# HMS_Olfactometer_v2_3.net
KiCad netlist of a schematic drawn in EAGLE
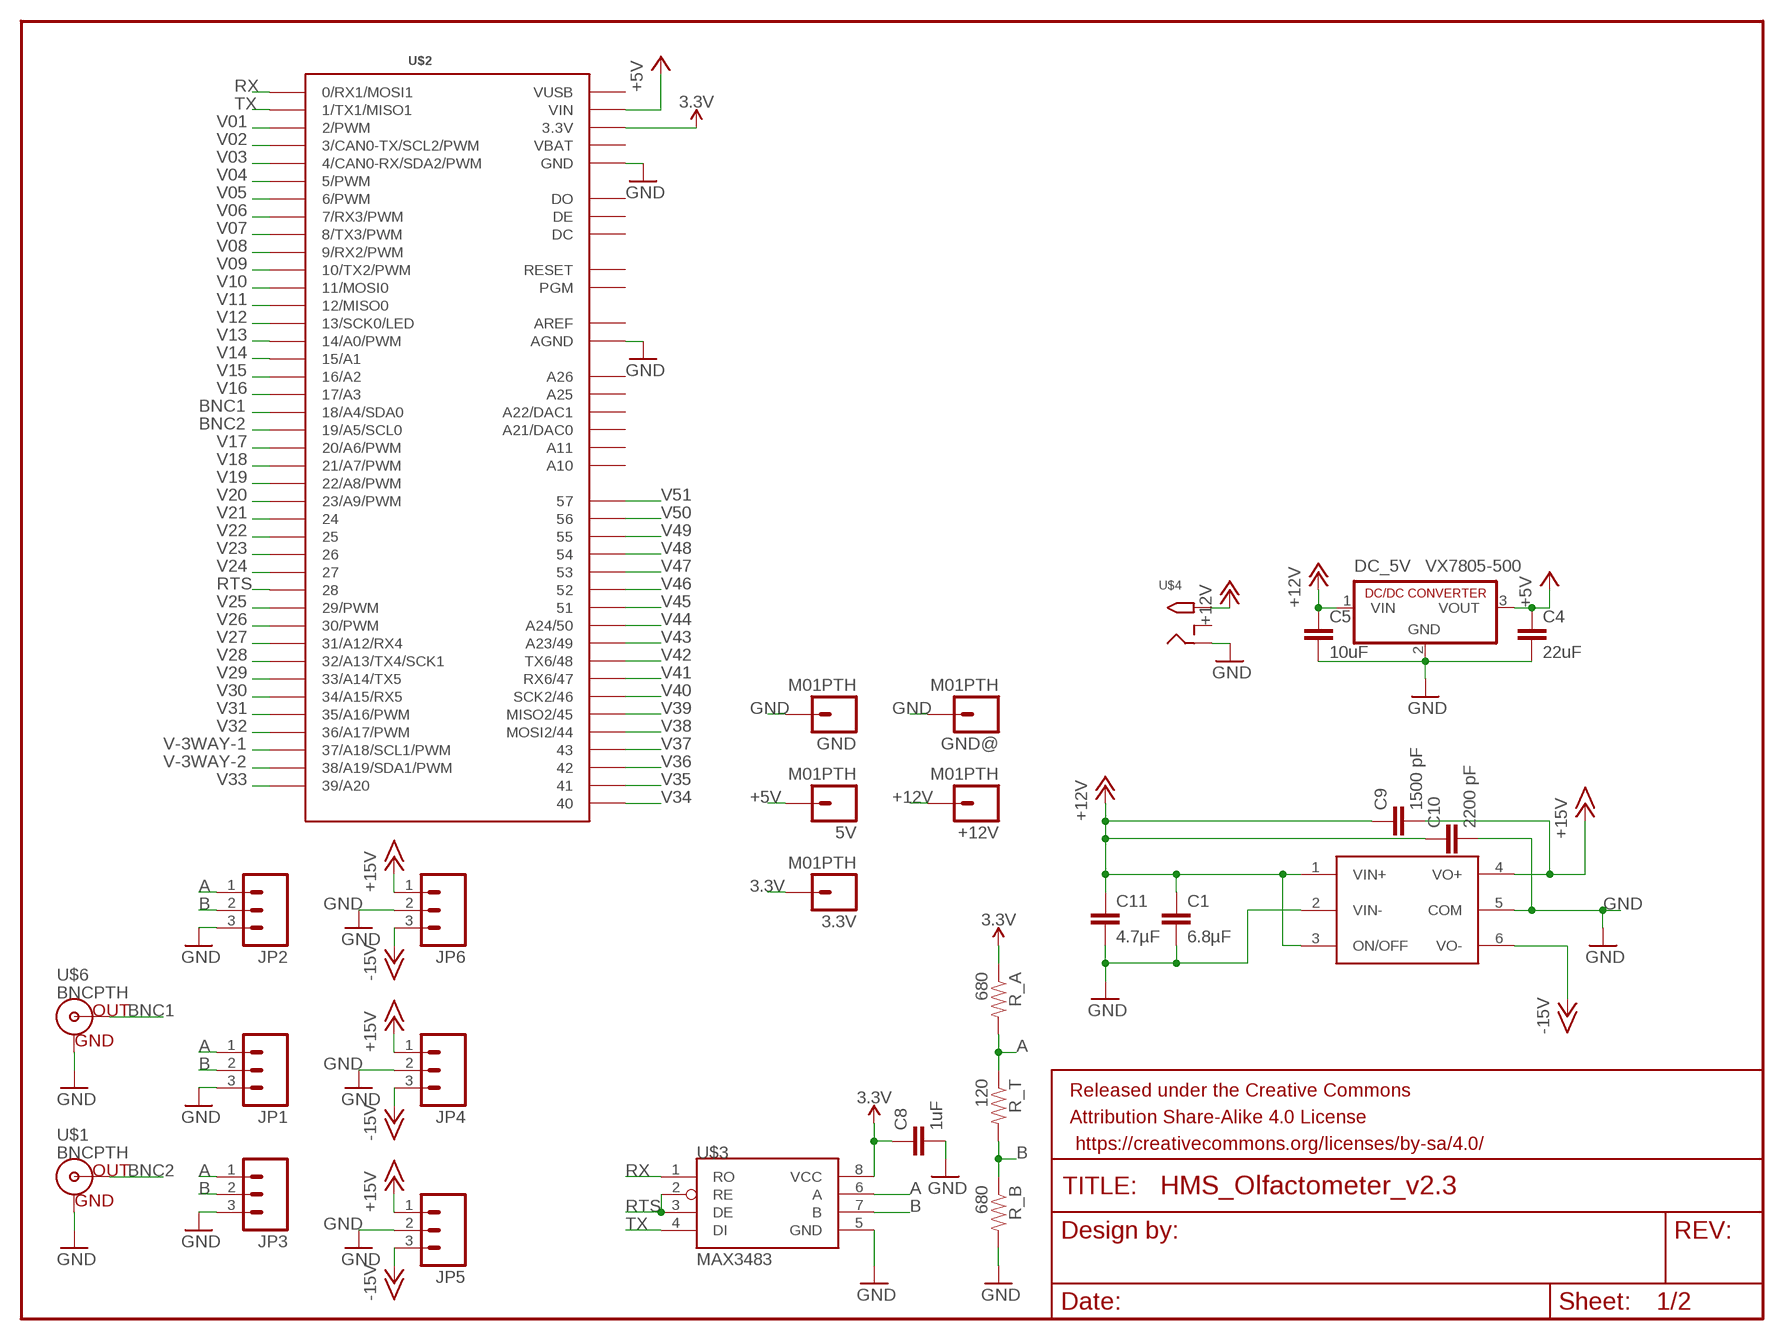
[diagram p0: schematic, sheet 1]
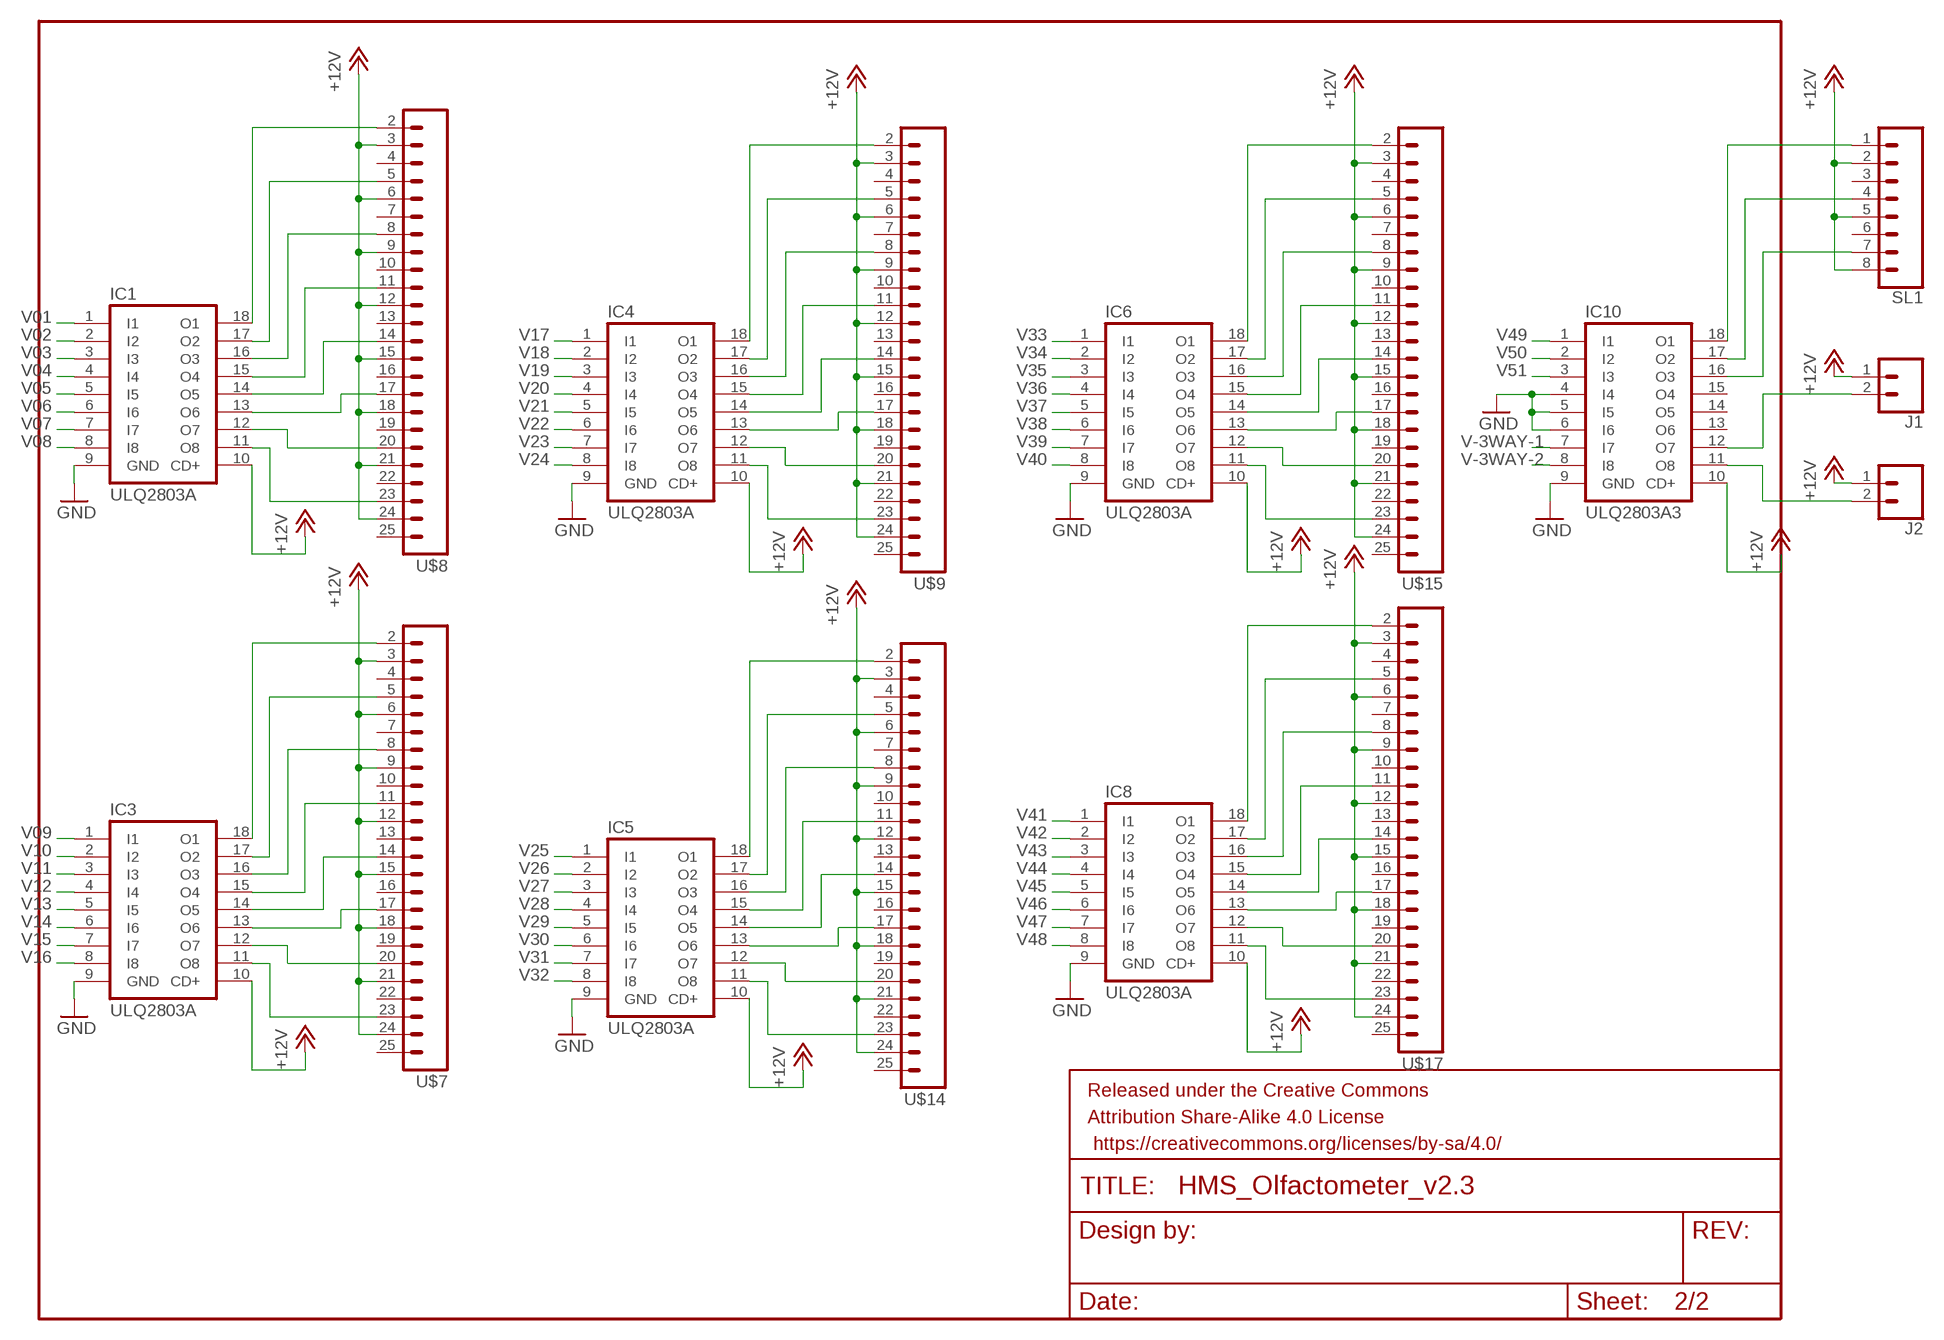
[diagram p1: schematic, sheet 2]

(export (version "E")
  (design (tool "Eeschema 10.0.6"))
  (components
    (comp (ref "+12V")
      (value "M01PTH")
      (footprint "eagle-import:1X01")
      (libsource (lib "eagle-import") (part "M01PTH"))
    )
    (comp (ref "3.3V")
      (value "M01PTH")
      (footprint "eagle-import:1X01")
      (libsource (lib "eagle-import") (part "M01PTH"))
    )
    (comp (ref "5V")
      (value "M01PTH")
      (footprint "eagle-import:1X01")
      (libsource (lib "eagle-import") (part "M01PTH"))
    )
    (comp (ref "C1")
      (value "6.8µF")
      (footprint "eagle-import:C1812")
      (libsource (lib "eagle-import") (part "C-EUC1812"))
    )
    (comp (ref "C4")
      (value "22uF")
      (footprint "eagle-import:1206")
      (libsource (lib "eagle-import") (part "10UF-6.3V-20%(1206)"))
    )
    (comp (ref "C5")
      (value "10uF")
      (footprint "eagle-import:1206")
      (libsource (lib "eagle-import") (part "CAP1206"))
    )
    (comp (ref "C8")
      (value "1uF")
      (footprint "eagle-import:1206")
      (libsource (lib "eagle-import") (part "CAP1206"))
    )
    (comp (ref "C9")
      (value "1500 pF")
      (footprint "eagle-import:C1206")
      (libsource (lib "eagle-import") (part "C-EUC1206"))
    )
    (comp (ref "C10")
      (value "2200 pF")
      (footprint "eagle-import:C1206")
      (libsource (lib "eagle-import") (part "C-EUC1206"))
    )
    (comp (ref "C11")
      (value "4.7µF")
      (footprint "eagle-import:C1812")
      (libsource (lib "eagle-import") (part "C-EUC1812"))
    )
    (comp (ref "DC_+/-15V")
      (value "XPPOWER_+/-15V_60W_DC-DC_SUPPLY")
      (footprint "eagle-import:XPPOWER_60W_JTL60_DC_DC_POWER_SUPPLY")
      (libsource (lib "eagle-import") (part "XPPOWER_+/-15V_60W_DC-DC_SUPPLY"))
    )
    (comp (ref "DC_5V")
      (value "VX7805-500")
      (footprint "eagle-import:SIP3")
      (libsource (lib "eagle-import") (part "R-78C-1.012"))
    )
    (comp (ref "FRAME1")
      (value "FRAME-LETTER")
      (footprint "eagle-import:CREATIVE_COMMONS")
      (libsource (lib "eagle-import") (part "FRAME-LETTER"))
    )
    (comp (ref "GND")
      (value "M01PTH")
      (footprint "eagle-import:1X01")
      (libsource (lib "eagle-import") (part "M01PTH"))
    )
    (comp (ref "GND@")
      (value "M01PTH")
      (footprint "eagle-import:1X01")
      (libsource (lib "eagle-import") (part "M01PTH"))
    )
    (comp (ref "JP1")
      (value "M03POLAR")
      (footprint "eagle-import:MOLEX-1X3")
      (libsource (lib "eagle-import") (part "M03POLAR"))
    )
    (comp (ref "JP2")
      (value "M03POLAR")
      (footprint "eagle-import:MOLEX-1X3")
      (libsource (lib "eagle-import") (part "M03POLAR"))
    )
    (comp (ref "JP3")
      (value "M03POLAR")
      (footprint "eagle-import:MOLEX-1X3")
      (libsource (lib "eagle-import") (part "M03POLAR"))
    )
    (comp (ref "JP4")
      (value "M03SCREW")
      (footprint "eagle-import:SCREWTERMINAL-3.5MM-3")
      (libsource (lib "eagle-import") (part "M03SCREW"))
    )
    (comp (ref "JP5")
      (value "M03SCREW")
      (footprint "eagle-import:SCREWTERMINAL-3.5MM-3")
      (libsource (lib "eagle-import") (part "M03SCREW"))
    )
    (comp (ref "JP6")
      (value "M03SCREW")
      (footprint "eagle-import:SCREWTERMINAL-3.5MM-3")
      (libsource (lib "eagle-import") (part "M03SCREW"))
    )
    (comp (ref "R_A")
      (value "680")
      (footprint "eagle-import:AXIAL-0.5")
      (libsource (lib "eagle-import") (part "RESISTORPTH-1/2W"))
    )
    (comp (ref "R_B")
      (value "680")
      (footprint "eagle-import:AXIAL-0.5")
      (libsource (lib "eagle-import") (part "RESISTORPTH-1/2W"))
    )
    (comp (ref "R_T")
      (value "120")
      (footprint "eagle-import:AXIAL-0.5")
      (libsource (lib "eagle-import") (part "RESISTORPTH-1/2W"))
    )
    (comp (ref "U$1")
      (value "BNCPTH")
      (footprint "eagle-import:BNC")
      (libsource (lib "eagle-import") (part "BNCPTH"))
    )
    (comp (ref "U$2")
      (value "TEENSY_3.5_ALL_PINS&PADS")
      (footprint "eagle-import:TEENSY_3.5_ALL_PINS&PADS")
      (libsource (lib "eagle-import") (part "TEENSY_3.5_ALL_PINS&PADS"))
    )
    (comp (ref "U$3")
      (value "MAX3483")
      (footprint "eagle-import:DIL08")
      (fields (field (name "SPICEPREFIX") "X"))
      (libsource (lib "eagle-import") (part "MAX485DIL"))
    )
    (comp (ref "U$4")
      (value "2.1MMJACKTHM")
      (footprint "eagle-import:PJ-102A")
      (libsource (lib "eagle-import") (part "2.1MMJACKTHM"))
    )
    (comp (ref "U$6")
      (value "BNCPTH")
      (footprint "eagle-import:BNC")
      (libsource (lib "eagle-import") (part "BNCPTH"))
    )
    (comp (ref "FRAME2")
      (value "FRAME-LETTER")
      (footprint "eagle-import:CREATIVE_COMMONS")
      (libsource (lib "eagle-import") (part "FRAME-LETTER"))
    )
    (comp (ref "IC1")
      (value "ULQ2803A")
      (footprint "eagle-import:DIL18")
      (libsource (lib "eagle-import") (part "ULN2803A"))
    )
    (comp (ref "IC3")
      (value "ULQ2803A")
      (footprint "eagle-import:DIL18")
      (libsource (lib "eagle-import") (part "ULN2803A"))
    )
    (comp (ref "IC4")
      (value "ULQ2803A")
      (footprint "eagle-import:DIL18")
      (libsource (lib "eagle-import") (part "ULN2803A"))
    )
    (comp (ref "IC5")
      (value "ULQ2803A")
      (footprint "eagle-import:DIL18")
      (libsource (lib "eagle-import") (part "ULN2803A"))
    )
    (comp (ref "IC6")
      (value "ULQ2803A")
      (footprint "eagle-import:DIL18")
      (libsource (lib "eagle-import") (part "ULN2803A"))
    )
    (comp (ref "IC8")
      (value "ULQ2803A")
      (footprint "eagle-import:DIL18")
      (libsource (lib "eagle-import") (part "ULN2803A"))
    )
    (comp (ref "IC10")
      (value "ULQ2803A3")
      (footprint "eagle-import:DIL18")
      (libsource (lib "eagle-import") (part "ULN2803A"))
    )
    (comp (ref "J1")
      (value "CONN_02")
      (footprint "eagle-import:1X02")
      (libsource (lib "eagle-import") (part "CONN_02"))
    )
    (comp (ref "J2")
      (value "CONN_02")
      (footprint "eagle-import:1X02")
      (libsource (lib "eagle-import") (part "CONN_02"))
    )
    (comp (ref "SL1")
      (value "CONN_08\"")
      (footprint "eagle-import:1X08")
      (libsource (lib "eagle-import") (part "CONN_08{dblquote}"))
    )
    (comp (ref "U$7")
      (value "M24")
      (footprint "eagle-import:1X24")
      (libsource (lib "eagle-import") (part "M24"))
    )
    (comp (ref "U$8")
      (value "M24")
      (footprint "eagle-import:1X24")
      (libsource (lib "eagle-import") (part "M24"))
    )
    (comp (ref "U$9")
      (value "M24")
      (footprint "eagle-import:1X24")
      (libsource (lib "eagle-import") (part "M24"))
    )
    (comp (ref "U$14")
      (value "M24")
      (footprint "eagle-import:1X24")
      (libsource (lib "eagle-import") (part "M24"))
    )
    (comp (ref "U$15")
      (value "M24")
      (footprint "eagle-import:1X24")
      (libsource (lib "eagle-import") (part "M24"))
    )
    (comp (ref "U$17")
      (value "M24")
      (footprint "eagle-import:1X24")
      (libsource (lib "eagle-import") (part "M24"))
    )
  )
  (nets
    (net (code "1") (name "+5V") (class "Default")
      (node (ref "5V") (pin "1") (pinfunction "1_1") (pintype "passive"))
      (node (ref "C4") (pin "1") (pinfunction "1_1") (pintype "passive"))
      (node (ref "DC_5V") (pin "3") (pinfunction "VOUT_3") (pintype "passive"))
      (node (ref "U$2") (pin "VIN") (pinfunction "VIN_VIN") (pintype "power_in"))
    )
    (net (code "2") (name "+12V") (class "Default")
      (node (ref "+12V") (pin "1") (pinfunction "1_1") (pintype "passive"))
      (node (ref "C1") (pin "1") (pinfunction "1_1") (pintype "passive"))
      (node (ref "C10") (pin "1") (pinfunction "1_1") (pintype "passive"))
      (node (ref "C11") (pin "1") (pinfunction "1_1") (pintype "passive"))
      (node (ref "C5") (pin "1") (pinfunction "1_1") (pintype "passive"))
      (node (ref "C9") (pin "1") (pinfunction "1_1") (pintype "passive"))
      (node (ref "DC_+/-15V") (pin "1") (pinfunction "VIN+_1") (pintype "passive"))
      (node (ref "DC_+/-15V") (pin "3") (pinfunction "ON/OFF_3") (pintype "bidirectional"))
      (node (ref "DC_5V") (pin "1") (pinfunction "VIN_1") (pintype "passive"))
      (node (ref "IC1") (pin "10") (pinfunction "CD+_10") (pintype "passive"))
      (node (ref "IC10") (pin "10") (pinfunction "CD+_10") (pintype "passive"))
      (node (ref "IC3") (pin "10") (pinfunction "CD+_10") (pintype "passive"))
      (node (ref "IC4") (pin "10") (pinfunction "CD+_10") (pintype "passive"))
      (node (ref "IC5") (pin "10") (pinfunction "CD+_10") (pintype "passive"))
      (node (ref "IC6") (pin "10") (pinfunction "CD+_10") (pintype "passive"))
      (node (ref "IC8") (pin "10") (pinfunction "CD+_10") (pintype "passive"))
      (node (ref "J1") (pin "1") (pinfunction "1_1") (pintype "passive"))
      (node (ref "J2") (pin "1") (pinfunction "1_1") (pintype "passive"))
      (node (ref "SL1") (pin "2") (pinfunction "2_2") (pintype "passive"))
      (node (ref "SL1") (pin "5") (pinfunction "5_5") (pintype "passive"))
      (node (ref "SL1") (pin "8") (pinfunction "8_8") (pintype "passive"))
      (node (ref "U$14") (pin "12") (pinfunction "12_12") (pintype "passive"))
      (node (ref "U$14") (pin "15") (pinfunction "15_15") (pintype "passive"))
      (node (ref "U$14") (pin "18") (pinfunction "18_18") (pintype "passive"))
      (node (ref "U$14") (pin "21") (pinfunction "21_21") (pintype "passive"))
      (node (ref "U$14") (pin "24") (pinfunction "24_24") (pintype "passive"))
      (node (ref "U$14") (pin "3") (pinfunction "3_3") (pintype "passive"))
      (node (ref "U$14") (pin "6") (pinfunction "6_6") (pintype "passive"))
      (node (ref "U$14") (pin "9") (pinfunction "9_9") (pintype "passive"))
      (node (ref "U$15") (pin "12") (pinfunction "12_12") (pintype "passive"))
      (node (ref "U$15") (pin "15") (pinfunction "15_15") (pintype "passive"))
      (node (ref "U$15") (pin "18") (pinfunction "18_18") (pintype "passive"))
      (node (ref "U$15") (pin "21") (pinfunction "21_21") (pintype "passive"))
      (node (ref "U$15") (pin "24") (pinfunction "24_24") (pintype "passive"))
      (node (ref "U$15") (pin "3") (pinfunction "3_3") (pintype "passive"))
      (node (ref "U$15") (pin "6") (pinfunction "6_6") (pintype "passive"))
      (node (ref "U$15") (pin "9") (pinfunction "9_9") (pintype "passive"))
      (node (ref "U$17") (pin "12") (pinfunction "12_12") (pintype "passive"))
      (node (ref "U$17") (pin "15") (pinfunction "15_15") (pintype "passive"))
      (node (ref "U$17") (pin "18") (pinfunction "18_18") (pintype "passive"))
      (node (ref "U$17") (pin "21") (pinfunction "21_21") (pintype "passive"))
      (node (ref "U$17") (pin "24") (pinfunction "24_24") (pintype "passive"))
      (node (ref "U$17") (pin "3") (pinfunction "3_3") (pintype "passive"))
      (node (ref "U$17") (pin "6") (pinfunction "6_6") (pintype "passive"))
      (node (ref "U$17") (pin "9") (pinfunction "9_9") (pintype "passive"))
      (node (ref "U$4") (pin "TIP") (pinfunction "TIP_TIP") (pintype "bidirectional"))
      (node (ref "U$7") (pin "12") (pinfunction "12_12") (pintype "passive"))
      (node (ref "U$7") (pin "15") (pinfunction "15_15") (pintype "passive"))
      (node (ref "U$7") (pin "18") (pinfunction "18_18") (pintype "passive"))
      (node (ref "U$7") (pin "21") (pinfunction "21_21") (pintype "passive"))
      (node (ref "U$7") (pin "24") (pinfunction "24_24") (pintype "passive"))
      (node (ref "U$7") (pin "3") (pinfunction "3_3") (pintype "passive"))
      (node (ref "U$7") (pin "6") (pinfunction "6_6") (pintype "passive"))
      (node (ref "U$7") (pin "9") (pinfunction "9_9") (pintype "passive"))
      (node (ref "U$8") (pin "12") (pinfunction "12_12") (pintype "passive"))
      (node (ref "U$8") (pin "15") (pinfunction "15_15") (pintype "passive"))
      (node (ref "U$8") (pin "18") (pinfunction "18_18") (pintype "passive"))
      (node (ref "U$8") (pin "21") (pinfunction "21_21") (pintype "passive"))
      (node (ref "U$8") (pin "24") (pinfunction "24_24") (pintype "passive"))
      (node (ref "U$8") (pin "3") (pinfunction "3_3") (pintype "passive"))
      (node (ref "U$8") (pin "6") (pinfunction "6_6") (pintype "passive"))
      (node (ref "U$8") (pin "9") (pinfunction "9_9") (pintype "passive"))
      (node (ref "U$9") (pin "12") (pinfunction "12_12") (pintype "passive"))
      (node (ref "U$9") (pin "15") (pinfunction "15_15") (pintype "passive"))
      (node (ref "U$9") (pin "18") (pinfunction "18_18") (pintype "passive"))
      (node (ref "U$9") (pin "21") (pinfunction "21_21") (pintype "passive"))
      (node (ref "U$9") (pin "24") (pinfunction "24_24") (pintype "passive"))
      (node (ref "U$9") (pin "3") (pinfunction "3_3") (pintype "passive"))
      (node (ref "U$9") (pin "6") (pinfunction "6_6") (pintype "passive"))
      (node (ref "U$9") (pin "9") (pinfunction "9_9") (pintype "passive"))
    )
    (net (code "3") (name "+15V") (class "Default")
      (node (ref "C9") (pin "2") (pinfunction "2_2") (pintype "passive"))
      (node (ref "DC_+/-15V") (pin "4") (pinfunction "VO+_4") (pintype "power_in"))
      (node (ref "JP4") (pin "1") (pinfunction "1_1") (pintype "passive"))
      (node (ref "JP5") (pin "1") (pinfunction "1_1") (pintype "passive"))
      (node (ref "JP6") (pin "1") (pinfunction "1_1") (pintype "passive"))
    )
    (net (code "4") (name "-15V") (class "Default")
      (node (ref "DC_+/-15V") (pin "6") (pinfunction "VO-_6") (pintype "power_in"))
      (node (ref "JP4") (pin "3") (pinfunction "3_3") (pintype "passive"))
      (node (ref "JP5") (pin "3") (pinfunction "3_3") (pintype "passive"))
      (node (ref "JP6") (pin "3") (pinfunction "3_3") (pintype "passive"))
    )
    (net (code "5") (name "3.3V") (class "Default")
      (node (ref "3.3V") (pin "1") (pinfunction "1_1") (pintype "passive"))
      (node (ref "C8") (pin "1") (pinfunction "1_1") (pintype "passive"))
      (node (ref "R_A") (pin "P$1") (pinfunction "1_P$1") (pintype "passive"))
      (node (ref "U$2") (pin "3.3V") (pinfunction "3.3V_3.3V") (pintype "power_in"))
      (node (ref "U$2") (pin "3.3V2") (pinfunction "3.3V_3.3V2") (pintype "power_in"))
      (node (ref "U$2") (pin "3.3V3") (pinfunction "3.3V_3.3V3") (pintype "power_in"))
      (node (ref "U$2") (pin "3.3V4") (pinfunction "3.3V_3.3V4") (pintype "power_in"))
      (node (ref "U$3") (pin "8") (pinfunction "VCC_8") (pintype "bidirectional"))
    )
    (net (code "6") (name "A") (class "Default")
      (node (ref "JP1") (pin "1") (pinfunction "1_1") (pintype "passive"))
      (node (ref "JP2") (pin "1") (pinfunction "1_1") (pintype "passive"))
      (node (ref "JP3") (pin "1") (pinfunction "1_1") (pintype "passive"))
      (node (ref "R_A") (pin "P$2") (pinfunction "2_P$2") (pintype "passive"))
      (node (ref "R_T") (pin "P$1") (pinfunction "1_P$1") (pintype "passive"))
      (node (ref "U$3") (pin "6") (pinfunction "A_6") (pintype "bidirectional"))
    )
    (net (code "7") (name "AREF") (class "Default")
      (node (ref "U$2") (pin "AREF") (pinfunction "AREF_AREF") (pintype "power_in"))
    )
    (net (code "8") (name "B") (class "Default")
      (node (ref "JP1") (pin "2") (pinfunction "2_2") (pintype "passive"))
      (node (ref "JP2") (pin "2") (pinfunction "2_2") (pintype "passive"))
      (node (ref "JP3") (pin "2") (pinfunction "2_2") (pintype "passive"))
      (node (ref "R_B") (pin "P$1") (pinfunction "1_P$1") (pintype "passive"))
      (node (ref "R_T") (pin "P$2") (pinfunction "2_P$2") (pintype "passive"))
      (node (ref "U$3") (pin "7") (pinfunction "B_7") (pintype "bidirectional"))
    )
    (net (code "9") (name "BNC1") (class "Default")
      (node (ref "U$2") (pin "18/A4") (pinfunction "18/A4/SDA0_18/A4") (pintype "bidirectional"))
      (node (ref "U$6") (pin "S") (pinfunction "OUT_S") (pintype "bidirectional"))
    )
    (net (code "10") (name "BNC2") (class "Default")
      (node (ref "U$1") (pin "S") (pinfunction "OUT_S") (pintype "bidirectional"))
      (node (ref "U$2") (pin "19/A5") (pinfunction "19/A5/SCL0_19/A5") (pintype "bidirectional"))
    )
    (net (code "11") (name "GND") (class "Default")
      (node (ref "C1") (pin "2") (pinfunction "2_2") (pintype "passive"))
      (node (ref "C10") (pin "2") (pinfunction "2_2") (pintype "passive"))
      (node (ref "C11") (pin "2") (pinfunction "2_2") (pintype "passive"))
      (node (ref "C4") (pin "2") (pinfunction "2_2") (pintype "passive"))
      (node (ref "C5") (pin "2") (pinfunction "2_2") (pintype "passive"))
      (node (ref "C8") (pin "2") (pinfunction "2_2") (pintype "passive"))
      (node (ref "DC_+/-15V") (pin "2") (pinfunction "VIN-_2") (pintype "power_in"))
      (node (ref "DC_+/-15V") (pin "5") (pinfunction "COM_5") (pintype "power_in"))
      (node (ref "DC_5V") (pin "2") (pinfunction "GND_2") (pintype "passive"))
      (node (ref "GND") (pin "1") (pinfunction "1_1") (pintype "passive"))
      (node (ref "GND@") (pin "1") (pinfunction "1_1") (pintype "passive"))
      (node (ref "IC1") (pin "9") (pinfunction "GND_9") (pintype "power_in"))
      (node (ref "IC10") (pin "4") (pinfunction "I4_4") (pintype "input"))
      (node (ref "IC10") (pin "5") (pinfunction "I5_5") (pintype "input"))
      (node (ref "IC10") (pin "6") (pinfunction "I6_6") (pintype "input"))
      (node (ref "IC10") (pin "9") (pinfunction "GND_9") (pintype "power_in"))
      (node (ref "IC3") (pin "9") (pinfunction "GND_9") (pintype "power_in"))
      (node (ref "IC4") (pin "9") (pinfunction "GND_9") (pintype "power_in"))
      (node (ref "IC5") (pin "9") (pinfunction "GND_9") (pintype "power_in"))
      (node (ref "IC6") (pin "9") (pinfunction "GND_9") (pintype "power_in"))
      (node (ref "IC8") (pin "9") (pinfunction "GND_9") (pintype "power_in"))
      (node (ref "JP1") (pin "3") (pinfunction "3_3") (pintype "passive"))
      (node (ref "JP2") (pin "3") (pinfunction "3_3") (pintype "passive"))
      (node (ref "JP3") (pin "3") (pinfunction "3_3") (pintype "passive"))
      (node (ref "JP4") (pin "2") (pinfunction "2_2") (pintype "passive"))
      (node (ref "JP5") (pin "2") (pinfunction "2_2") (pintype "passive"))
      (node (ref "JP6") (pin "2") (pinfunction "2_2") (pintype "passive"))
      (node (ref "R_B") (pin "P$2") (pinfunction "2_P$2") (pintype "passive"))
      (node (ref "U$1") (pin "GND") (pinfunction "GND_GND") (pintype "bidirectional"))
      (node (ref "U$2") (pin "AGND") (pinfunction "AGND_AGND") (pintype "power_in"))
      (node (ref "U$2") (pin "GND") (pinfunction "GND_GND") (pintype "power_in"))
      (node (ref "U$2") (pin "GND1") (pinfunction "GND_GND1") (pintype "power_in"))
      (node (ref "U$2") (pin "GND2") (pinfunction "GND_GND2") (pintype "power_in"))
      (node (ref "U$2") (pin "GND3") (pinfunction "GND_GND3") (pintype "power_in"))
      (node (ref "U$2") (pin "GND4") (pinfunction "GND_GND4") (pintype "power_in"))
      (node (ref "U$2") (pin "GND5") (pinfunction "GND_GND5") (pintype "power_in"))
      (node (ref "U$2") (pin "GND6") (pinfunction "GND_GND6") (pintype "power_in"))
      (node (ref "U$3") (pin "5") (pinfunction "GND_5") (pintype "bidirectional"))
      (node (ref "U$4") (pin "RING") (pinfunction "RING_RING") (pintype "bidirectional"))
      (node (ref "U$6") (pin "GND") (pinfunction "GND_GND") (pintype "bidirectional"))
    )
    (net (code "12") (name "Net-(IC1-O1)") (class "Default")
      (node (ref "IC1") (pin "18") (pinfunction "O1_18") (pintype "open_collector"))
      (node (ref "U$8") (pin "2") (pinfunction "2_2") (pintype "passive"))
    )
    (net (code "13") (name "Net-(IC1-O2)") (class "Default")
      (node (ref "IC1") (pin "17") (pinfunction "O2_17") (pintype "open_collector"))
      (node (ref "U$8") (pin "5") (pinfunction "5_5") (pintype "passive"))
    )
    (net (code "14") (name "Net-(IC1-O3)") (class "Default")
      (node (ref "IC1") (pin "16") (pinfunction "O3_16") (pintype "open_collector"))
      (node (ref "U$8") (pin "8") (pinfunction "8_8") (pintype "passive"))
    )
    (net (code "15") (name "Net-(IC1-O4)") (class "Default")
      (node (ref "IC1") (pin "15") (pinfunction "O4_15") (pintype "open_collector"))
      (node (ref "U$8") (pin "11") (pinfunction "11_11") (pintype "passive"))
    )
    (net (code "16") (name "Net-(IC1-O5)") (class "Default")
      (node (ref "IC1") (pin "14") (pinfunction "O5_14") (pintype "open_collector"))
      (node (ref "U$8") (pin "14") (pinfunction "14_14") (pintype "passive"))
    )
    (net (code "17") (name "Net-(IC1-O6)") (class "Default")
      (node (ref "IC1") (pin "13") (pinfunction "O6_13") (pintype "open_collector"))
      (node (ref "U$8") (pin "17") (pinfunction "17_17") (pintype "passive"))
    )
    (net (code "18") (name "Net-(IC1-O7)") (class "Default")
      (node (ref "IC1") (pin "12") (pinfunction "O7_12") (pintype "open_collector"))
      (node (ref "U$8") (pin "20") (pinfunction "20_20") (pintype "passive"))
    )
    (net (code "19") (name "Net-(IC1-O8)") (class "Default")
      (node (ref "IC1") (pin "11") (pinfunction "O8_11") (pintype "open_collector"))
      (node (ref "U$8") (pin "23") (pinfunction "23_23") (pintype "passive"))
    )
    (net (code "20") (name "Net-(IC3-O1)") (class "Default")
      (node (ref "IC3") (pin "18") (pinfunction "O1_18") (pintype "open_collector"))
      (node (ref "U$7") (pin "2") (pinfunction "2_2") (pintype "passive"))
    )
    (net (code "21") (name "Net-(IC3-O2)") (class "Default")
      (node (ref "IC3") (pin "17") (pinfunction "O2_17") (pintype "open_collector"))
      (node (ref "U$7") (pin "5") (pinfunction "5_5") (pintype "passive"))
    )
    (net (code "22") (name "Net-(IC3-O3)") (class "Default")
      (node (ref "IC3") (pin "16") (pinfunction "O3_16") (pintype "open_collector"))
      (node (ref "U$7") (pin "8") (pinfunction "8_8") (pintype "passive"))
    )
    (net (code "23") (name "Net-(IC3-O4)") (class "Default")
      (node (ref "IC3") (pin "15") (pinfunction "O4_15") (pintype "open_collector"))
      (node (ref "U$7") (pin "11") (pinfunction "11_11") (pintype "passive"))
    )
    (net (code "24") (name "Net-(IC3-O5)") (class "Default")
      (node (ref "IC3") (pin "14") (pinfunction "O5_14") (pintype "open_collector"))
      (node (ref "U$7") (pin "14") (pinfunction "14_14") (pintype "passive"))
    )
    (net (code "25") (name "Net-(IC3-O6)") (class "Default")
      (node (ref "IC3") (pin "13") (pinfunction "O6_13") (pintype "open_collector"))
      (node (ref "U$7") (pin "17") (pinfunction "17_17") (pintype "passive"))
    )
    (net (code "26") (name "Net-(IC3-O7)") (class "Default")
      (node (ref "IC3") (pin "12") (pinfunction "O7_12") (pintype "open_collector"))
      (node (ref "U$7") (pin "20") (pinfunction "20_20") (pintype "passive"))
    )
    (net (code "27") (name "Net-(IC3-O8)") (class "Default")
      (node (ref "IC3") (pin "11") (pinfunction "O8_11") (pintype "open_collector"))
      (node (ref "U$7") (pin "23") (pinfunction "23_23") (pintype "passive"))
    )
    (net (code "28") (name "Net-(IC4-O1)") (class "Default")
      (node (ref "IC4") (pin "18") (pinfunction "O1_18") (pintype "open_collector"))
      (node (ref "U$9") (pin "2") (pinfunction "2_2") (pintype "passive"))
    )
    (net (code "29") (name "Net-(IC4-O2)") (class "Default")
      (node (ref "IC4") (pin "17") (pinfunction "O2_17") (pintype "open_collector"))
      (node (ref "U$9") (pin "5") (pinfunction "5_5") (pintype "passive"))
    )
    (net (code "30") (name "Net-(IC4-O3)") (class "Default")
      (node (ref "IC4") (pin "16") (pinfunction "O3_16") (pintype "open_collector"))
      (node (ref "U$9") (pin "8") (pinfunction "8_8") (pintype "passive"))
    )
    (net (code "31") (name "Net-(IC4-O4)") (class "Default")
      (node (ref "IC4") (pin "15") (pinfunction "O4_15") (pintype "open_collector"))
      (node (ref "U$9") (pin "11") (pinfunction "11_11") (pintype "passive"))
    )
    (net (code "32") (name "Net-(IC4-O5)") (class "Default")
      (node (ref "IC4") (pin "14") (pinfunction "O5_14") (pintype "open_collector"))
      (node (ref "U$9") (pin "14") (pinfunction "14_14") (pintype "passive"))
    )
    (net (code "33") (name "Net-(IC4-O6)") (class "Default")
      (node (ref "IC4") (pin "13") (pinfunction "O6_13") (pintype "open_collector"))
      (node (ref "U$9") (pin "17") (pinfunction "17_17") (pintype "passive"))
    )
    (net (code "34") (name "Net-(IC4-O7)") (class "Default")
      (node (ref "IC4") (pin "12") (pinfunction "O7_12") (pintype "open_collector"))
      (node (ref "U$9") (pin "20") (pinfunction "20_20") (pintype "passive"))
    )
    (net (code "35") (name "Net-(IC4-O8)") (class "Default")
      (node (ref "IC4") (pin "11") (pinfunction "O8_11") (pintype "open_collector"))
      (node (ref "U$9") (pin "23") (pinfunction "23_23") (pintype "passive"))
    )
    (net (code "36") (name "Net-(IC5-O1)") (class "Default")
      (node (ref "IC5") (pin "18") (pinfunction "O1_18") (pintype "open_collector"))
      (node (ref "U$14") (pin "2") (pinfunction "2_2") (pintype "passive"))
    )
    (net (code "37") (name "Net-(IC5-O2)") (class "Default")
      (node (ref "IC5") (pin "17") (pinfunction "O2_17") (pintype "open_collector"))
      (node (ref "U$14") (pin "5") (pinfunction "5_5") (pintype "passive"))
    )
    (net (code "38") (name "Net-(IC5-O3)") (class "Default")
      (node (ref "IC5") (pin "16") (pinfunction "O3_16") (pintype "open_collector"))
      (node (ref "U$14") (pin "8") (pinfunction "8_8") (pintype "passive"))
    )
    (net (code "39") (name "Net-(IC5-O4)") (class "Default")
      (node (ref "IC5") (pin "15") (pinfunction "O4_15") (pintype "open_collector"))
      (node (ref "U$14") (pin "11") (pinfunction "11_11") (pintype "passive"))
    )
    (net (code "40") (name "Net-(IC5-O5)") (class "Default")
      (node (ref "IC5") (pin "14") (pinfunction "O5_14") (pintype "open_collector"))
      (node (ref "U$14") (pin "14") (pinfunction "14_14") (pintype "passive"))
    )
    (net (code "41") (name "Net-(IC5-O6)") (class "Default")
      (node (ref "IC5") (pin "13") (pinfunction "O6_13") (pintype "open_collector"))
      (node (ref "U$14") (pin "17") (pinfunction "17_17") (pintype "passive"))
    )
    (net (code "42") (name "Net-(IC5-O7)") (class "Default")
      (node (ref "IC5") (pin "12") (pinfunction "O7_12") (pintype "open_collector"))
      (node (ref "U$14") (pin "20") (pinfunction "20_20") (pintype "passive"))
    )
    (net (code "43") (name "Net-(IC5-O8)") (class "Default")
      (node (ref "IC5") (pin "11") (pinfunction "O8_11") (pintype "open_collector"))
      (node (ref "U$14") (pin "23") (pinfunction "23_23") (pintype "passive"))
    )
    (net (code "44") (name "Net-(IC6-O1)") (class "Default")
      (node (ref "IC6") (pin "18") (pinfunction "O1_18") (pintype "open_collector"))
      (node (ref "U$15") (pin "2") (pinfunction "2_2") (pintype "passive"))
    )
    (net (code "45") (name "Net-(IC6-O2)") (class "Default")
      (node (ref "IC6") (pin "17") (pinfunction "O2_17") (pintype "open_collector"))
      (node (ref "U$15") (pin "5") (pinfunction "5_5") (pintype "passive"))
    )
    (net (code "46") (name "Net-(IC6-O3)") (class "Default")
      (node (ref "IC6") (pin "16") (pinfunction "O3_16") (pintype "open_collector"))
      (node (ref "U$15") (pin "8") (pinfunction "8_8") (pintype "passive"))
    )
    (net (code "47") (name "Net-(IC6-O4)") (class "Default")
      (node (ref "IC6") (pin "15") (pinfunction "O4_15") (pintype "open_collector"))
      (node (ref "U$15") (pin "11") (pinfunction "11_11") (pintype "passive"))
    )
    (net (code "48") (name "Net-(IC6-O5)") (class "Default")
      (node (ref "IC6") (pin "14") (pinfunction "O5_14") (pintype "open_collector"))
      (node (ref "U$15") (pin "14") (pinfunction "14_14") (pintype "passive"))
    )
    (net (code "49") (name "Net-(IC6-O6)") (class "Default")
      (node (ref "IC6") (pin "13") (pinfunction "O6_13") (pintype "open_collector"))
      (node (ref "U$15") (pin "17") (pinfunction "17_17") (pintype "passive"))
    )
    (net (code "50") (name "Net-(IC6-O7)") (class "Default")
      (node (ref "IC6") (pin "12") (pinfunction "O7_12") (pintype "open_collector"))
      (node (ref "U$15") (pin "20") (pinfunction "20_20") (pintype "passive"))
    )
    (net (code "51") (name "Net-(IC6-O8)") (class "Default")
      (node (ref "IC6") (pin "11") (pinfunction "O8_11") (pintype "open_collector"))
      (node (ref "U$15") (pin "23") (pinfunction "23_23") (pintype "passive"))
    )
    (net (code "52") (name "Net-(IC8-O1)") (class "Default")
      (node (ref "IC8") (pin "18") (pinfunction "O1_18") (pintype "open_collector"))
      (node (ref "U$17") (pin "2") (pinfunction "2_2") (pintype "passive"))
    )
    (net (code "53") (name "Net-(IC8-O2)") (class "Default")
      (node (ref "IC8") (pin "17") (pinfunction "O2_17") (pintype "open_collector"))
      (node (ref "U$17") (pin "5") (pinfunction "5_5") (pintype "passive"))
    )
    (net (code "54") (name "Net-(IC8-O3)") (class "Default")
      (node (ref "IC8") (pin "16") (pinfunction "O3_16") (pintype "open_collector"))
      (node (ref "U$17") (pin "8") (pinfunction "8_8") (pintype "passive"))
    )
    (net (code "55") (name "Net-(IC8-O4)") (class "Default")
      (node (ref "IC8") (pin "15") (pinfunction "O4_15") (pintype "open_collector"))
      (node (ref "U$17") (pin "11") (pinfunction "11_11") (pintype "passive"))
    )
    (net (code "56") (name "Net-(IC8-O5)") (class "Default")
      (node (ref "IC8") (pin "14") (pinfunction "O5_14") (pintype "open_collector"))
      (node (ref "U$17") (pin "14") (pinfunction "14_14") (pintype "passive"))
    )
    (net (code "57") (name "Net-(IC8-O6)") (class "Default")
      (node (ref "IC8") (pin "13") (pinfunction "O6_13") (pintype "open_collector"))
      (node (ref "U$17") (pin "17") (pinfunction "17_17") (pintype "passive"))
    )
    (net (code "58") (name "Net-(IC8-O7)") (class "Default")
      (node (ref "IC8") (pin "12") (pinfunction "O7_12") (pintype "open_collector"))
      (node (ref "U$17") (pin "20") (pinfunction "20_20") (pintype "passive"))
    )
    (net (code "59") (name "Net-(IC8-O8)") (class "Default")
      (node (ref "IC8") (pin "11") (pinfunction "O8_11") (pintype "open_collector"))
      (node (ref "U$17") (pin "23") (pinfunction "23_23") (pintype "passive"))
    )
    (net (code "60") (name "Net-(IC10-O1)") (class "Default")
      (node (ref "IC10") (pin "18") (pinfunction "O1_18") (pintype "open_collector"))
      (node (ref "SL1") (pin "1") (pinfunction "1_1") (pintype "passive"))
    )
    (net (code "61") (name "Net-(IC10-O2)") (class "Default")
      (node (ref "IC10") (pin "17") (pinfunction "O2_17") (pintype "open_collector"))
      (node (ref "SL1") (pin "4") (pinfunction "4_4") (pintype "passive"))
    )
    (net (code "62") (name "Net-(IC10-O3)") (class "Default")
      (node (ref "IC10") (pin "16") (pinfunction "O3_16") (pintype "open_collector"))
      (node (ref "SL1") (pin "7") (pinfunction "7_7") (pintype "passive"))
    )
    (net (code "63") (name "Net-(IC10-O7)") (class "Default")
      (node (ref "IC10") (pin "12") (pinfunction "O7_12") (pintype "open_collector"))
      (node (ref "J1") (pin "2") (pinfunction "2_2") (pintype "passive"))
    )
    (net (code "64") (name "Net-(IC10-O8)") (class "Default")
      (node (ref "IC10") (pin "11") (pinfunction "O8_11") (pintype "open_collector"))
      (node (ref "J2") (pin "2") (pinfunction "2_2") (pintype "passive"))
    )
    (net (code "65") (name "RTS") (class "Default")
      (node (ref "U$2") (pin "28") (pinfunction "28_28") (pintype "bidirectional"))
      (node (ref "U$3") (pin "2") (pinfunction "RE_2") (pintype "bidirectional"))
      (node (ref "U$3") (pin "3") (pinfunction "DE_3") (pintype "bidirectional"))
    )
    (net (code "66") (name "RX") (class "Default")
      (node (ref "U$2") (pin "0") (pinfunction "0/RX1/MOSI1_0") (pintype "bidirectional"))
      (node (ref "U$3") (pin "1") (pinfunction "RO_1") (pintype "bidirectional"))
    )
    (net (code "67") (name "TX") (class "Default")
      (node (ref "U$2") (pin "1") (pinfunction "1/TX1/MISO1_1") (pintype "bidirectional"))
      (node (ref "U$3") (pin "4") (pinfunction "DI_4") (pintype "bidirectional"))
    )
    (net (code "68") (name "V-3WAY-1") (class "Default")
      (node (ref "IC10") (pin "7") (pinfunction "I7_7") (pintype "input"))
      (node (ref "U$2") (pin "37/A18") (pinfunction "37/A18/SCL1/PWM_37/A18") (pintype "bidirectional"))
    )
    (net (code "69") (name "V-3WAY-2") (class "Default")
      (node (ref "IC10") (pin "8") (pinfunction "I8_8") (pintype "input"))
      (node (ref "U$2") (pin "38/A19") (pinfunction "38/A19/SDA1/PWM_38/A19") (pintype "bidirectional"))
    )
    (net (code "70") (name "V01") (class "Default")
      (node (ref "IC1") (pin "1") (pinfunction "I1_1") (pintype "input"))
      (node (ref "U$2") (pin "2") (pinfunction "2/PWM_2") (pintype "bidirectional"))
    )
    (net (code "71") (name "V02") (class "Default")
      (node (ref "IC1") (pin "2") (pinfunction "I2_2") (pintype "input"))
      (node (ref "U$2") (pin "3") (pinfunction "3/CAN0-TX/SCL2/PWM_3") (pintype "bidirectional"))
    )
    (net (code "72") (name "V03") (class "Default")
      (node (ref "IC1") (pin "3") (pinfunction "I3_3") (pintype "input"))
      (node (ref "U$2") (pin "4") (pinfunction "4/CAN0-RX/SDA2/PWM_4") (pintype "bidirectional"))
    )
    (net (code "73") (name "V04") (class "Default")
      (node (ref "IC1") (pin "4") (pinfunction "I4_4") (pintype "input"))
      (node (ref "U$2") (pin "5") (pinfunction "5/PWM_5") (pintype "bidirectional"))
    )
    (net (code "74") (name "V05") (class "Default")
      (node (ref "IC1") (pin "5") (pinfunction "I5_5") (pintype "input"))
      (node (ref "U$2") (pin "6") (pinfunction "6/PWM_6") (pintype "bidirectional"))
    )
    (net (code "75") (name "V06") (class "Default")
      (node (ref "IC1") (pin "6") (pinfunction "I6_6") (pintype "input"))
      (node (ref "U$2") (pin "7") (pinfunction "7/RX3/PWM_7") (pintype "bidirectional"))
    )
    (net (code "76") (name "V07") (class "Default")
      (node (ref "IC1") (pin "7") (pinfunction "I7_7") (pintype "input"))
      (node (ref "U$2") (pin "8") (pinfunction "8/TX3/PWM_8") (pintype "bidirectional"))
    )
    (net (code "77") (name "V08") (class "Default")
      (node (ref "IC1") (pin "8") (pinfunction "I8_8") (pintype "input"))
      (node (ref "U$2") (pin "9") (pinfunction "9/RX2/PWM_9") (pintype "bidirectional"))
    )
    (net (code "78") (name "V09") (class "Default")
      (node (ref "IC3") (pin "1") (pinfunction "I1_1") (pintype "input"))
      (node (ref "U$2") (pin "10") (pinfunction "10/TX2/PWM_10") (pintype "bidirectional"))
    )
    (net (code "79") (name "V10") (class "Default")
      (node (ref "IC3") (pin "2") (pinfunction "I2_2") (pintype "input"))
      (node (ref "U$2") (pin "11") (pinfunction "11/MOSI0_11") (pintype "bidirectional"))
    )
    (net (code "80") (name "V11") (class "Default")
      (node (ref "IC3") (pin "3") (pinfunction "I3_3") (pintype "input"))
      (node (ref "U$2") (pin "12") (pinfunction "12/MISO0_12") (pintype "bidirectional"))
    )
    (net (code "81") (name "V12") (class "Default")
      (node (ref "IC3") (pin "4") (pinfunction "I4_4") (pintype "input"))
      (node (ref "U$2") (pin "13") (pinfunction "13/SCK0/LED_13") (pintype "bidirectional"))
    )
    (net (code "82") (name "V13") (class "Default")
      (node (ref "IC3") (pin "5") (pinfunction "I5_5") (pintype "input"))
      (node (ref "U$2") (pin "14/A0") (pinfunction "14/A0/PWM_14/A0") (pintype "bidirectional"))
    )
    (net (code "83") (name "V14") (class "Default")
      (node (ref "IC3") (pin "6") (pinfunction "I6_6") (pintype "input"))
      (node (ref "U$2") (pin "15/A1") (pinfunction "15/A1_15/A1") (pintype "bidirectional"))
    )
    (net (code "84") (name "V15") (class "Default")
      (node (ref "IC3") (pin "7") (pinfunction "I7_7") (pintype "input"))
      (node (ref "U$2") (pin "16/A2") (pinfunction "16/A2_16/A2") (pintype "bidirectional"))
    )
    (net (code "85") (name "V16") (class "Default")
      (node (ref "IC3") (pin "8") (pinfunction "I8_8") (pintype "input"))
      (node (ref "U$2") (pin "17/A3") (pinfunction "17/A3_17/A3") (pintype "bidirectional"))
    )
    (net (code "86") (name "V17") (class "Default")
      (node (ref "IC4") (pin "1") (pinfunction "I1_1") (pintype "input"))
      (node (ref "U$2") (pin "20/A6") (pinfunction "20/A6/PWM_20/A6") (pintype "bidirectional"))
    )
    (net (code "87") (name "V18") (class "Default")
      (node (ref "IC4") (pin "2") (pinfunction "I2_2") (pintype "input"))
      (node (ref "U$2") (pin "21/A7") (pinfunction "21/A7/PWM_21/A7") (pintype "bidirectional"))
    )
    (net (code "88") (name "V19") (class "Default")
      (node (ref "IC4") (pin "3") (pinfunction "I3_3") (pintype "input"))
      (node (ref "U$2") (pin "22/A8") (pinfunction "22/A8/PWM_22/A8") (pintype "bidirectional"))
    )
    (net (code "89") (name "V20") (class "Default")
      (node (ref "IC4") (pin "4") (pinfunction "I4_4") (pintype "input"))
      (node (ref "U$2") (pin "23/A9") (pinfunction "23/A9/PWM_23/A9") (pintype "bidirectional"))
    )
    (net (code "90") (name "V21") (class "Default")
      (node (ref "IC4") (pin "5") (pinfunction "I5_5") (pintype "input"))
      (node (ref "U$2") (pin "24") (pinfunction "24_24") (pintype "bidirectional"))
    )
    (net (code "91") (name "V22") (class "Default")
      (node (ref "IC4") (pin "6") (pinfunction "I6_6") (pintype "input"))
      (node (ref "U$2") (pin "25") (pinfunction "25_25") (pintype "bidirectional"))
    )
    (net (code "92") (name "V23") (class "Default")
      (node (ref "IC4") (pin "7") (pinfunction "I7_7") (pintype "input"))
      (node (ref "U$2") (pin "26") (pinfunction "26_26") (pintype "bidirectional"))
    )
    (net (code "93") (name "V24") (class "Default")
      (node (ref "IC4") (pin "8") (pinfunction "I8_8") (pintype "input"))
      (node (ref "U$2") (pin "27") (pinfunction "27_27") (pintype "bidirectional"))
    )
    (net (code "94") (name "V25") (class "Default")
      (node (ref "IC5") (pin "1") (pinfunction "I1_1") (pintype "input"))
      (node (ref "U$2") (pin "29") (pinfunction "29/PWM_29") (pintype "bidirectional"))
    )
    (net (code "95") (name "V26") (class "Default")
      (node (ref "IC5") (pin "2") (pinfunction "I2_2") (pintype "input"))
      (node (ref "U$2") (pin "30") (pinfunction "30/PWM_30") (pintype "bidirectional"))
    )
    (net (code "96") (name "V27") (class "Default")
      (node (ref "IC5") (pin "3") (pinfunction "I3_3") (pintype "input"))
      (node (ref "U$2") (pin "31/A12") (pinfunction "31/A12/RX4_31/A12") (pintype "bidirectional"))
    )
    (net (code "97") (name "V28") (class "Default")
      (node (ref "IC5") (pin "4") (pinfunction "I4_4") (pintype "input"))
      (node (ref "U$2") (pin "32/A13") (pinfunction "32/A13/TX4/SCK1_32/A13") (pintype "bidirectional"))
    )
    (net (code "98") (name "V29") (class "Default")
      (node (ref "IC5") (pin "5") (pinfunction "I5_5") (pintype "input"))
      (node (ref "U$2") (pin "33/A14") (pinfunction "33/A14/TX5_33/A14") (pintype "bidirectional"))
    )
    (net (code "99") (name "V30") (class "Default")
      (node (ref "IC5") (pin "6") (pinfunction "I6_6") (pintype "input"))
      (node (ref "U$2") (pin "34/A15") (pinfunction "34/A15/RX5_34/A15") (pintype "bidirectional"))
    )
    (net (code "100") (name "V31") (class "Default")
      (node (ref "IC5") (pin "7") (pinfunction "I7_7") (pintype "input"))
      (node (ref "U$2") (pin "35/A16") (pinfunction "35/A16/PWM_35/A16") (pintype "bidirectional"))
    )
    (net (code "101") (name "V32") (class "Default")
      (node (ref "IC5") (pin "8") (pinfunction "I8_8") (pintype "input"))
      (node (ref "U$2") (pin "36/A17") (pinfunction "36/A17/PWM_36/A17") (pintype "bidirectional"))
    )
    (net (code "102") (name "V33") (class "Default")
      (node (ref "IC6") (pin "1") (pinfunction "I1_1") (pintype "input"))
      (node (ref "U$2") (pin "39/A20") (pinfunction "39/A20_39/A20") (pintype "bidirectional"))
    )
    (net (code "103") (name "V34") (class "Default")
      (node (ref "IC6") (pin "2") (pinfunction "I2_2") (pintype "input"))
      (node (ref "U$2") (pin "40") (pinfunction "40_40") (pintype "bidirectional"))
    )
    (net (code "104") (name "V35") (class "Default")
      (node (ref "IC6") (pin "3") (pinfunction "I3_3") (pintype "input"))
      (node (ref "U$2") (pin "41") (pinfunction "41_41") (pintype "bidirectional"))
    )
    (net (code "105") (name "V36") (class "Default")
      (node (ref "IC6") (pin "4") (pinfunction "I4_4") (pintype "input"))
      (node (ref "U$2") (pin "42") (pinfunction "42_42") (pintype "bidirectional"))
    )
    (net (code "106") (name "V37") (class "Default")
      (node (ref "IC6") (pin "5") (pinfunction "I5_5") (pintype "input"))
      (node (ref "U$2") (pin "43") (pinfunction "43_43") (pintype "bidirectional"))
    )
    (net (code "107") (name "V38") (class "Default")
      (node (ref "IC6") (pin "6") (pinfunction "I6_6") (pintype "input"))
      (node (ref "U$2") (pin "44") (pinfunction "MOSI2/44_44") (pintype "bidirectional"))
    )
    (net (code "108") (name "V39") (class "Default")
      (node (ref "IC6") (pin "7") (pinfunction "I7_7") (pintype "input"))
      (node (ref "U$2") (pin "45") (pinfunction "MISO2/45_45") (pintype "bidirectional"))
    )
    (net (code "109") (name "V40") (class "Default")
      (node (ref "IC6") (pin "8") (pinfunction "I8_8") (pintype "input"))
      (node (ref "U$2") (pin "46") (pinfunction "SCK2/46_46") (pintype "bidirectional"))
    )
    (net (code "110") (name "V41") (class "Default")
      (node (ref "IC8") (pin "1") (pinfunction "I1_1") (pintype "input"))
      (node (ref "U$2") (pin "47") (pinfunction "RX6/47_47") (pintype "bidirectional"))
    )
    (net (code "111") (name "V42") (class "Default")
      (node (ref "IC8") (pin "2") (pinfunction "I2_2") (pintype "input"))
      (node (ref "U$2") (pin "48") (pinfunction "TX6/48_48") (pintype "bidirectional"))
    )
    (net (code "112") (name "V43") (class "Default")
      (node (ref "IC8") (pin "3") (pinfunction "I3_3") (pintype "input"))
      (node (ref "U$2") (pin "49") (pinfunction "A23/49_49") (pintype "bidirectional"))
    )
    (net (code "113") (name "V44") (class "Default")
      (node (ref "IC8") (pin "4") (pinfunction "I4_4") (pintype "input"))
      (node (ref "U$2") (pin "50") (pinfunction "A24/50_50") (pintype "bidirectional"))
    )
    (net (code "114") (name "V45") (class "Default")
      (node (ref "IC8") (pin "5") (pinfunction "I5_5") (pintype "input"))
      (node (ref "U$2") (pin "51") (pinfunction "51_51") (pintype "bidirectional"))
    )
    (net (code "115") (name "V46") (class "Default")
      (node (ref "IC8") (pin "6") (pinfunction "I6_6") (pintype "input"))
      (node (ref "U$2") (pin "52") (pinfunction "52_52") (pintype "bidirectional"))
    )
    (net (code "116") (name "V47") (class "Default")
      (node (ref "IC8") (pin "7") (pinfunction "I7_7") (pintype "input"))
      (node (ref "U$2") (pin "53") (pinfunction "53_53") (pintype "bidirectional"))
    )
    (net (code "117") (name "V48") (class "Default")
      (node (ref "IC8") (pin "8") (pinfunction "I8_8") (pintype "input"))
      (node (ref "U$2") (pin "54") (pinfunction "54_54") (pintype "bidirectional"))
    )
    (net (code "118") (name "V49") (class "Default")
      (node (ref "IC10") (pin "1") (pinfunction "I1_1") (pintype "input"))
      (node (ref "U$2") (pin "55") (pinfunction "55_55") (pintype "bidirectional"))
    )
    (net (code "119") (name "V50") (class "Default")
      (node (ref "IC10") (pin "2") (pinfunction "I2_2") (pintype "input"))
      (node (ref "U$2") (pin "56") (pinfunction "56_56") (pintype "bidirectional"))
    )
    (net (code "120") (name "V51") (class "Default")
      (node (ref "IC10") (pin "3") (pinfunction "I3_3") (pintype "input"))
      (node (ref "U$2") (pin "57") (pinfunction "57_57") (pintype "bidirectional"))
    )
    (net (code "121") (name "VBAT") (class "Default")
      (node (ref "U$2") (pin "VBAT") (pinfunction "VBAT_VBAT") (pintype "power_in"))
    )
    (net (code "122") (name "VUSB") (class "Default")
      (node (ref "U$2") (pin "VUSB") (pinfunction "VUSB_VUSB") (pintype "power_in"))
    )
    (net (code "123") (name "unconnected-(IC10-O4-Pad15)") (class "Default")
      (node (ref "IC10") (pin "15") (pinfunction "O4_15") (pintype "open_collector"))
    )
    (net (code "124") (name "unconnected-(IC10-O5-Pad14)") (class "Default")
      (node (ref "IC10") (pin "14") (pinfunction "O5_14") (pintype "open_collector"))
    )
    (net (code "125") (name "unconnected-(IC10-O6-Pad13)") (class "Default")
      (node (ref "IC10") (pin "13") (pinfunction "O6_13") (pintype "open_collector"))
    )
    (net (code "126") (name "unconnected-(SL1-Pad3)") (class "Default")
      (node (ref "SL1") (pin "3") (pinfunction "3_3") (pintype "passive"))
    )
    (net (code "127") (name "unconnected-(SL1-Pad6)") (class "Default")
      (node (ref "SL1") (pin "6") (pinfunction "6_6") (pintype "passive"))
    )
    (net (code "128") (name "unconnected-(U$2-A21{slash}DAC0-PadA21)") (class "Default")
      (node (ref "U$2") (pin "A21") (pinfunction "A21/DAC0_A21") (pintype "bidirectional"))
    )
    (net (code "129") (name "unconnected-(U$2-A22{slash}DAC1-PadA22)") (class "Default")
      (node (ref "U$2") (pin "A22") (pinfunction "A22/DAC1_A22") (pintype "bidirectional"))
    )
    (net (code "130") (name "unconnected-(U$2-PadA10)") (class "Default")
      (node (ref "U$2") (pin "A10") (pinfunction "A10_A10") (pintype "bidirectional"))
    )
    (net (code "131") (name "unconnected-(U$2-PadA11)") (class "Default")
      (node (ref "U$2") (pin "A11") (pinfunction "A11_A11") (pintype "bidirectional"))
    )
    (net (code "132") (name "unconnected-(U$2-PadA25)") (class "Default")
      (node (ref "U$2") (pin "A25") (pinfunction "A25_A25") (pintype "bidirectional"))
    )
    (net (code "133") (name "unconnected-(U$2-PadA26)") (class "Default")
      (node (ref "U$2") (pin "A26") (pinfunction "A26_A26") (pintype "bidirectional"))
    )
    (net (code "134") (name "unconnected-(U$2-PadDC)") (class "Default")
      (node (ref "U$2") (pin "DC") (pinfunction "DC_DC") (pintype "bidirectional"))
    )
    (net (code "135") (name "unconnected-(U$2-PadDE)") (class "Default")
      (node (ref "U$2") (pin "DE") (pinfunction "DE_DE") (pintype "bidirectional"))
    )
    (net (code "136") (name "unconnected-(U$2-PadDO)") (class "Default")
      (node (ref "U$2") (pin "DO") (pinfunction "DO_DO") (pintype "bidirectional"))
    )
    (net (code "137") (name "unconnected-(U$2-PadPGM)") (class "Default")
      (node (ref "U$2") (pin "PGM") (pinfunction "PGM_PGM") (pintype "bidirectional"))
    )
    (net (code "138") (name "unconnected-(U$2-PadRESET)") (class "Default")
      (node (ref "U$2") (pin "RESET") (pinfunction "RESET_RESET") (pintype "bidirectional"))
    )
    (net (code "139") (name "unconnected-(U$4-PadRING_SW)") (class "Default")
      (node (ref "U$4") (pin "RING_SW") (pinfunction "RING_SW_RING_SW") (pintype "bidirectional"))
    )
    (net (code "140") (name "unconnected-(U$7-Pad4)") (class "Default")
      (node (ref "U$7") (pin "4") (pinfunction "4_4") (pintype "passive"))
    )
    (net (code "141") (name "unconnected-(U$7-Pad7)") (class "Default")
      (node (ref "U$7") (pin "7") (pinfunction "7_7") (pintype "passive"))
    )
    (net (code "142") (name "unconnected-(U$7-Pad10)") (class "Default")
      (node (ref "U$7") (pin "10") (pinfunction "10_10") (pintype "passive"))
    )
    (net (code "143") (name "unconnected-(U$7-Pad13)") (class "Default")
      (node (ref "U$7") (pin "13") (pinfunction "13_13") (pintype "passive"))
    )
    (net (code "144") (name "unconnected-(U$7-Pad16)") (class "Default")
      (node (ref "U$7") (pin "16") (pinfunction "16_16") (pintype "passive"))
    )
    (net (code "145") (name "unconnected-(U$7-Pad19)") (class "Default")
      (node (ref "U$7") (pin "19") (pinfunction "19_19") (pintype "passive"))
    )
    (net (code "146") (name "unconnected-(U$7-Pad22)") (class "Default")
      (node (ref "U$7") (pin "22") (pinfunction "22_22") (pintype "passive"))
    )
    (net (code "147") (name "unconnected-(U$7-Pad25)") (class "Default")
      (node (ref "U$7") (pin "25") (pinfunction "25_25") (pintype "passive"))
    )
    (net (code "148") (name "unconnected-(U$8-Pad4)") (class "Default")
      (node (ref "U$8") (pin "4") (pinfunction "4_4") (pintype "passive"))
    )
    (net (code "149") (name "unconnected-(U$8-Pad7)") (class "Default")
      (node (ref "U$8") (pin "7") (pinfunction "7_7") (pintype "passive"))
    )
    (net (code "150") (name "unconnected-(U$8-Pad10)") (class "Default")
      (node (ref "U$8") (pin "10") (pinfunction "10_10") (pintype "passive"))
    )
    (net (code "151") (name "unconnected-(U$8-Pad13)") (class "Default")
      (node (ref "U$8") (pin "13") (pinfunction "13_13") (pintype "passive"))
    )
    (net (code "152") (name "unconnected-(U$8-Pad16)") (class "Default")
      (node (ref "U$8") (pin "16") (pinfunction "16_16") (pintype "passive"))
    )
    (net (code "153") (name "unconnected-(U$8-Pad19)") (class "Default")
      (node (ref "U$8") (pin "19") (pinfunction "19_19") (pintype "passive"))
    )
    (net (code "154") (name "unconnected-(U$8-Pad22)") (class "Default")
      (node (ref "U$8") (pin "22") (pinfunction "22_22") (pintype "passive"))
    )
    (net (code "155") (name "unconnected-(U$8-Pad25)") (class "Default")
      (node (ref "U$8") (pin "25") (pinfunction "25_25") (pintype "passive"))
    )
    (net (code "156") (name "unconnected-(U$9-Pad4)") (class "Default")
      (node (ref "U$9") (pin "4") (pinfunction "4_4") (pintype "passive"))
    )
    (net (code "157") (name "unconnected-(U$9-Pad7)") (class "Default")
      (node (ref "U$9") (pin "7") (pinfunction "7_7") (pintype "passive"))
    )
    (net (code "158") (name "unconnected-(U$9-Pad10)") (class "Default")
      (node (ref "U$9") (pin "10") (pinfunction "10_10") (pintype "passive"))
    )
    (net (code "159") (name "unconnected-(U$9-Pad13)") (class "Default")
      (node (ref "U$9") (pin "13") (pinfunction "13_13") (pintype "passive"))
    )
    (net (code "160") (name "unconnected-(U$9-Pad16)") (class "Default")
      (node (ref "U$9") (pin "16") (pinfunction "16_16") (pintype "passive"))
    )
    (net (code "161") (name "unconnected-(U$9-Pad19)") (class "Default")
      (node (ref "U$9") (pin "19") (pinfunction "19_19") (pintype "passive"))
    )
    (net (code "162") (name "unconnected-(U$9-Pad22)") (class "Default")
      (node (ref "U$9") (pin "22") (pinfunction "22_22") (pintype "passive"))
    )
    (net (code "163") (name "unconnected-(U$9-Pad25)") (class "Default")
      (node (ref "U$9") (pin "25") (pinfunction "25_25") (pintype "passive"))
    )
    (net (code "164") (name "unconnected-(U$14-Pad4)") (class "Default")
      (node (ref "U$14") (pin "4") (pinfunction "4_4") (pintype "passive"))
    )
    (net (code "165") (name "unconnected-(U$14-Pad7)") (class "Default")
      (node (ref "U$14") (pin "7") (pinfunction "7_7") (pintype "passive"))
    )
    (net (code "166") (name "unconnected-(U$14-Pad10)") (class "Default")
      (node (ref "U$14") (pin "10") (pinfunction "10_10") (pintype "passive"))
    )
    (net (code "167") (name "unconnected-(U$14-Pad13)") (class "Default")
      (node (ref "U$14") (pin "13") (pinfunction "13_13") (pintype "passive"))
    )
    (net (code "168") (name "unconnected-(U$14-Pad16)") (class "Default")
      (node (ref "U$14") (pin "16") (pinfunction "16_16") (pintype "passive"))
    )
    (net (code "169") (name "unconnected-(U$14-Pad19)") (class "Default")
      (node (ref "U$14") (pin "19") (pinfunction "19_19") (pintype "passive"))
    )
    (net (code "170") (name "unconnected-(U$14-Pad22)") (class "Default")
      (node (ref "U$14") (pin "22") (pinfunction "22_22") (pintype "passive"))
    )
    (net (code "171") (name "unconnected-(U$14-Pad25)") (class "Default")
      (node (ref "U$14") (pin "25") (pinfunction "25_25") (pintype "passive"))
    )
    (net (code "172") (name "unconnected-(U$15-Pad4)") (class "Default")
      (node (ref "U$15") (pin "4") (pinfunction "4_4") (pintype "passive"))
    )
    (net (code "173") (name "unconnected-(U$15-Pad7)") (class "Default")
      (node (ref "U$15") (pin "7") (pinfunction "7_7") (pintype "passive"))
    )
    (net (code "174") (name "unconnected-(U$15-Pad10)") (class "Default")
      (node (ref "U$15") (pin "10") (pinfunction "10_10") (pintype "passive"))
    )
    (net (code "175") (name "unconnected-(U$15-Pad13)") (class "Default")
      (node (ref "U$15") (pin "13") (pinfunction "13_13") (pintype "passive"))
    )
    (net (code "176") (name "unconnected-(U$15-Pad16)") (class "Default")
      (node (ref "U$15") (pin "16") (pinfunction "16_16") (pintype "passive"))
    )
    (net (code "177") (name "unconnected-(U$15-Pad19)") (class "Default")
      (node (ref "U$15") (pin "19") (pinfunction "19_19") (pintype "passive"))
    )
    (net (code "178") (name "unconnected-(U$15-Pad22)") (class "Default")
      (node (ref "U$15") (pin "22") (pinfunction "22_22") (pintype "passive"))
    )
    (net (code "179") (name "unconnected-(U$15-Pad25)") (class "Default")
      (node (ref "U$15") (pin "25") (pinfunction "25_25") (pintype "passive"))
    )
    (net (code "180") (name "unconnected-(U$17-Pad4)") (class "Default")
      (node (ref "U$17") (pin "4") (pinfunction "4_4") (pintype "passive"))
    )
    (net (code "181") (name "unconnected-(U$17-Pad7)") (class "Default")
      (node (ref "U$17") (pin "7") (pinfunction "7_7") (pintype "passive"))
    )
    (net (code "182") (name "unconnected-(U$17-Pad10)") (class "Default")
      (node (ref "U$17") (pin "10") (pinfunction "10_10") (pintype "passive"))
    )
    (net (code "183") (name "unconnected-(U$17-Pad13)") (class "Default")
      (node (ref "U$17") (pin "13") (pinfunction "13_13") (pintype "passive"))
    )
    (net (code "184") (name "unconnected-(U$17-Pad16)") (class "Default")
      (node (ref "U$17") (pin "16") (pinfunction "16_16") (pintype "passive"))
    )
    (net (code "185") (name "unconnected-(U$17-Pad19)") (class "Default")
      (node (ref "U$17") (pin "19") (pinfunction "19_19") (pintype "passive"))
    )
    (net (code "186") (name "unconnected-(U$17-Pad22)") (class "Default")
      (node (ref "U$17") (pin "22") (pinfunction "22_22") (pintype "passive"))
    )
    (net (code "187") (name "unconnected-(U$17-Pad25)") (class "Default")
      (node (ref "U$17") (pin "25") (pinfunction "25_25") (pintype "passive"))
    )
  )
)
